# ft232.net
KiCad netlist of a schematic drawn in EAGLE
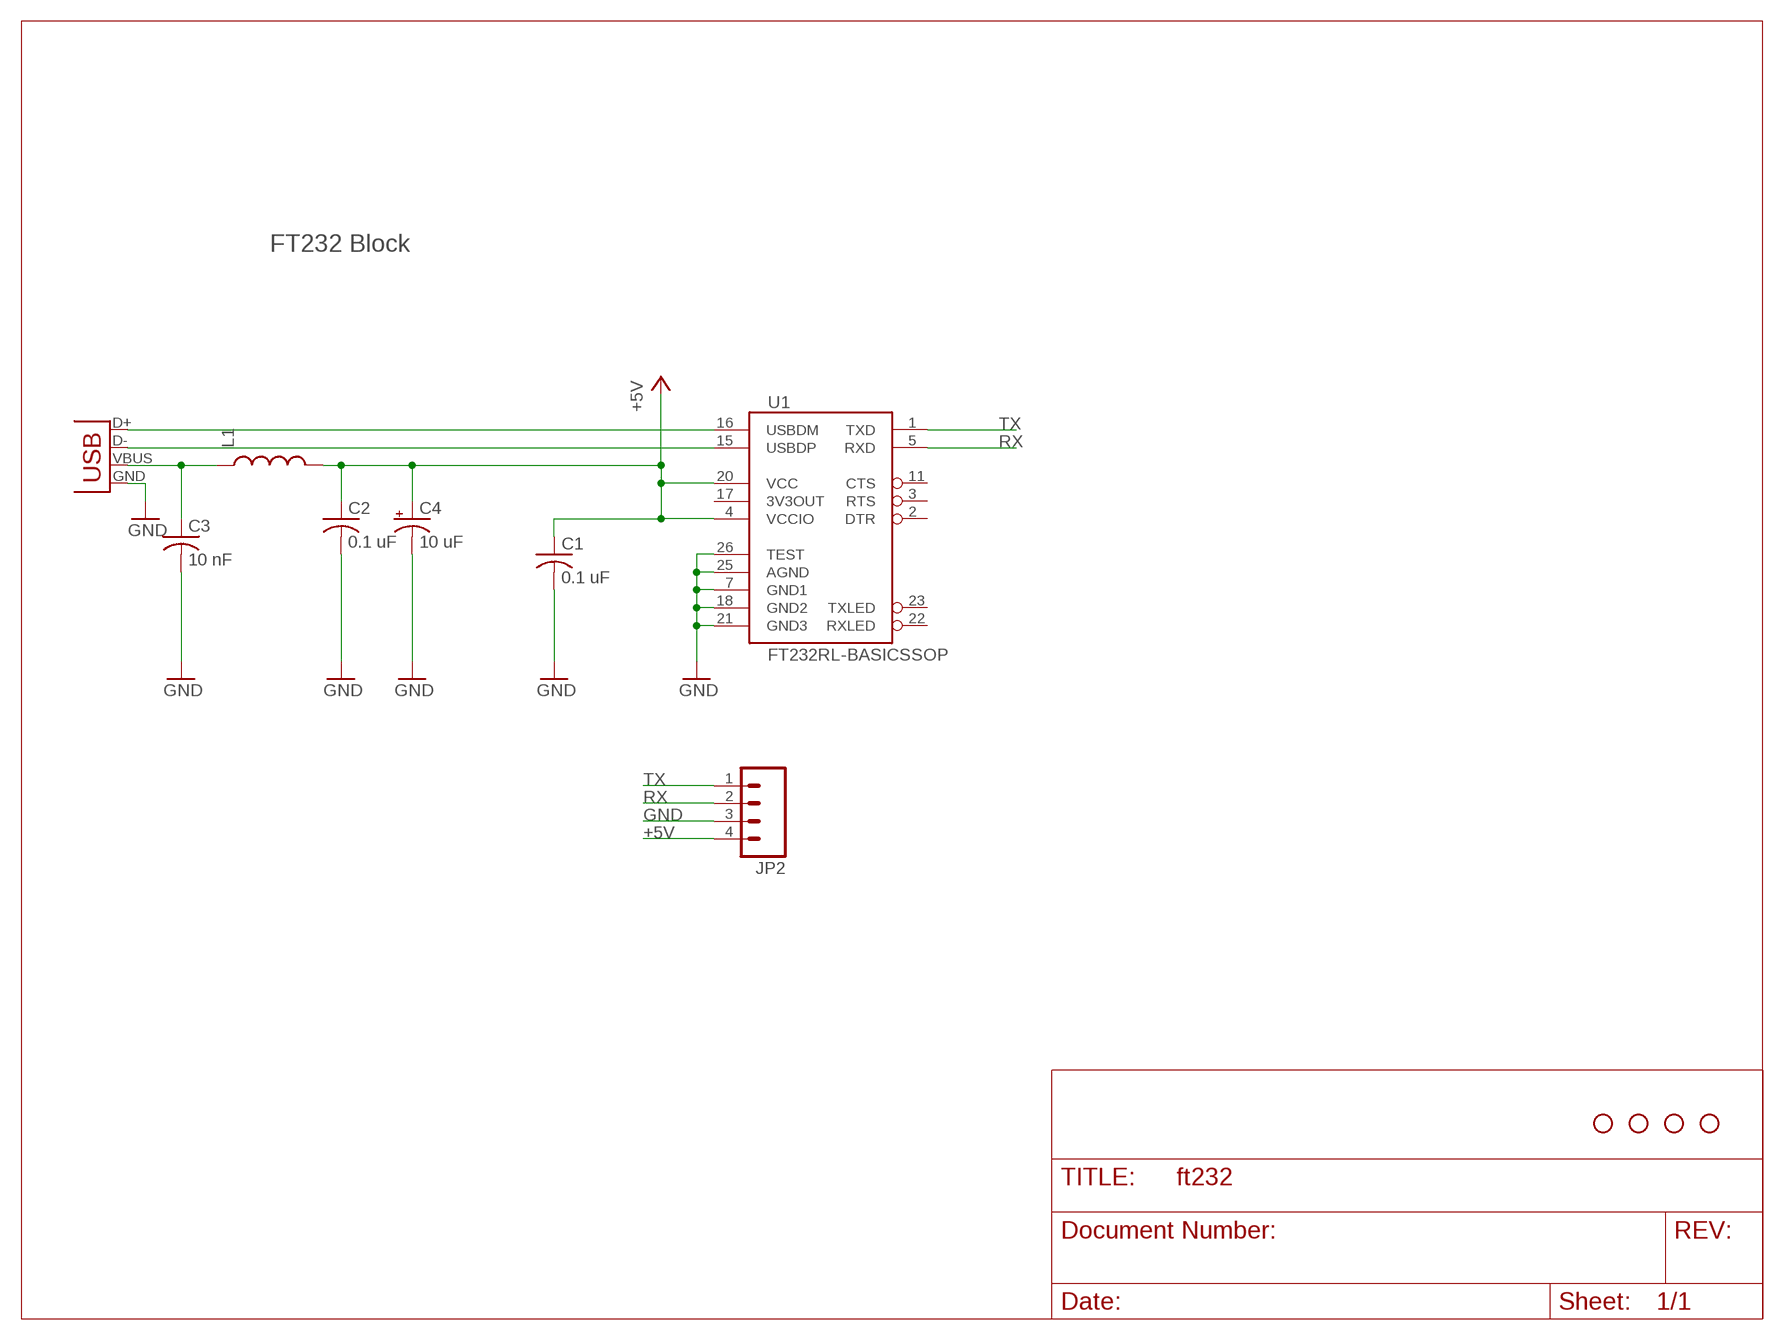
[diagram p0: schematic, sheet 1]

(export (version "E")
  (design (tool "Eeschema 10.0.6"))
  (components
    (comp (ref "C1")
      (value "0.1 uF")
      (footprint "eagle-import:C0603")
      (libsource (lib "eagle-import") (part "C-USC0603"))
    )
    (comp (ref "C2")
      (value "0.1 uF")
      (footprint "eagle-import:C0603")
      (libsource (lib "eagle-import") (part "C-USC0603"))
    )
    (comp (ref "C3")
      (value "10 nF")
      (footprint "eagle-import:C0603")
      (libsource (lib "eagle-import") (part "C-USC0603"))
    )
    (comp (ref "C4")
      (value "10 uF")
      (footprint "eagle-import:EIA3216")
      (libsource (lib "eagle-import") (part "CAP_POL1206"))
    )
    (comp (ref "JP1")
      (value "USB-B")
      (footprint "eagle-import:USB-B-PTH")
      (libsource (lib "eagle-import") (part "USBPTH"))
    )
    (comp (ref "JP2")
      (value "M04PTH")
      (footprint "eagle-import:1X04")
      (libsource (lib "eagle-import") (part "M04PTH"))
    )
    (comp (ref "L1")
      (value "INDUCTOR0603")
      (footprint "eagle-import:0603")
      (libsource (lib "eagle-import") (part "INDUCTOR0603"))
    )
    (comp (ref "STANDOFF1")
      (value "STAND-OFF")
      (footprint "eagle-import:STAND-OFF")
      (libsource (lib "eagle-import") (part "STAND-OFF"))
    )
    (comp (ref "STANDOFF2")
      (value "STAND-OFF")
      (footprint "eagle-import:STAND-OFF")
      (libsource (lib "eagle-import") (part "STAND-OFF"))
    )
    (comp (ref "STANDOFF3")
      (value "STAND-OFF")
      (footprint "eagle-import:STAND-OFF")
      (libsource (lib "eagle-import") (part "STAND-OFF"))
    )
    (comp (ref "STANDOFF4")
      (value "STAND-OFF")
      (footprint "eagle-import:STAND-OFF")
      (libsource (lib "eagle-import") (part "STAND-OFF"))
    )
    (comp (ref "U1")
      (value "FT232RL-BASICSSOP")
      (footprint "eagle-import:SSOP28DB")
      (libsource (lib "eagle-import") (part "FT232RL-BASICSSOP"))
    )
  )
  (nets
    (net (code "1") (name "+5V") (class "Default")
      (node (ref "C1") (pin "1") (pinfunction "1_1") (pintype "passive"))
      (node (ref "C2") (pin "1") (pinfunction "1_1") (pintype "passive"))
      (node (ref "C4") (pin "A") (pinfunction "+_A") (pintype "passive"))
      (node (ref "JP2") (pin "4") (pinfunction "4_4") (pintype "passive"))
      (node (ref "L1") (pin "2") (pinfunction "2_2") (pintype "passive"))
      (node (ref "U1") (pin "20") (pinfunction "VCC_20") (pintype "power_in"))
      (node (ref "U1") (pin "4") (pinfunction "VCCIO_4") (pintype "power_in"))
    )
    (net (code "2") (name "/RX") (class "Default")
      (node (ref "JP2") (pin "2") (pinfunction "2_2") (pintype "passive"))
      (node (ref "U1") (pin "5") (pinfunction "RXD_5") (pintype "input"))
    )
    (net (code "3") (name "/TX") (class "Default")
      (node (ref "JP2") (pin "1") (pinfunction "1_1") (pintype "passive"))
      (node (ref "U1") (pin "1") (pinfunction "TXD_1") (pintype "output"))
    )
    (net (code "4") (name "GND") (class "Default")
      (node (ref "C1") (pin "2") (pinfunction "2_2") (pintype "passive"))
      (node (ref "C2") (pin "2") (pinfunction "2_2") (pintype "passive"))
      (node (ref "C3") (pin "2") (pinfunction "2_2") (pintype "passive"))
      (node (ref "C4") (pin "C") (pinfunction "-_C") (pintype "passive"))
      (node (ref "JP1") (pin "GND") (pinfunction "GND_GND") (pintype "bidirectional"))
      (node (ref "JP2") (pin "3") (pinfunction "3_3") (pintype "passive"))
      (node (ref "U1") (pin "18") (pinfunction "GND2_18") (pintype "power_in"))
      (node (ref "U1") (pin "21") (pinfunction "GND3_21") (pintype "power_in"))
      (node (ref "U1") (pin "25") (pinfunction "AGND_25") (pintype "power_in"))
      (node (ref "U1") (pin "26") (pinfunction "TEST_26") (pintype "input"))
      (node (ref "U1") (pin "7") (pinfunction "GND1_7") (pintype "power_in"))
    )
    (net (code "5") (name "Net-(C3-Pad1)") (class "Default")
      (node (ref "C3") (pin "1") (pinfunction "1_1") (pintype "passive"))
      (node (ref "JP1") (pin "VBUS") (pinfunction "VBUS_VBUS") (pintype "bidirectional"))
      (node (ref "L1") (pin "1") (pinfunction "1_1") (pintype "passive"))
    )
    (net (code "6") (name "Net-(U1-USBDM)") (class "Default")
      (node (ref "JP1") (pin "D+") (pinfunction "D+_D+") (pintype "bidirectional"))
      (node (ref "U1") (pin "16") (pinfunction "USBDM_16") (pintype "bidirectional"))
    )
    (net (code "7") (name "Net-(U1-USBDP)") (class "Default")
      (node (ref "JP1") (pin "D-") (pinfunction "D-_D-") (pintype "bidirectional"))
      (node (ref "U1") (pin "15") (pinfunction "USBDP_15") (pintype "bidirectional"))
    )
    (net (code "8") (name "unconnected-(U1-3V3OUT-Pad17)") (class "Default")
      (node (ref "U1") (pin "17") (pinfunction "3V3OUT_17") (pintype "output"))
    )
    (net (code "9") (name "unconnected-(U1-CTS-Pad11)") (class "Default")
      (node (ref "U1") (pin "11") (pinfunction "CTS_11") (pintype "bidirectional"))
    )
    (net (code "10") (name "unconnected-(U1-DTR-Pad2)") (class "Default")
      (node (ref "U1") (pin "2") (pinfunction "DTR_2") (pintype "bidirectional"))
    )
    (net (code "11") (name "unconnected-(U1-RTS-Pad3)") (class "Default")
      (node (ref "U1") (pin "3") (pinfunction "RTS_3") (pintype "bidirectional"))
    )
    (net (code "12") (name "unconnected-(U1-RXLED-Pad22)") (class "Default")
      (node (ref "U1") (pin "22") (pinfunction "RXLED_22") (pintype "bidirectional"))
    )
    (net (code "13") (name "unconnected-(U1-TXLED-Pad23)") (class "Default")
      (node (ref "U1") (pin "23") (pinfunction "TXLED_23") (pintype "bidirectional"))
    )
  )
)
